# Pressure_Sensor_Breakout.net
KiCad netlist of a schematic drawn in Altium Designer
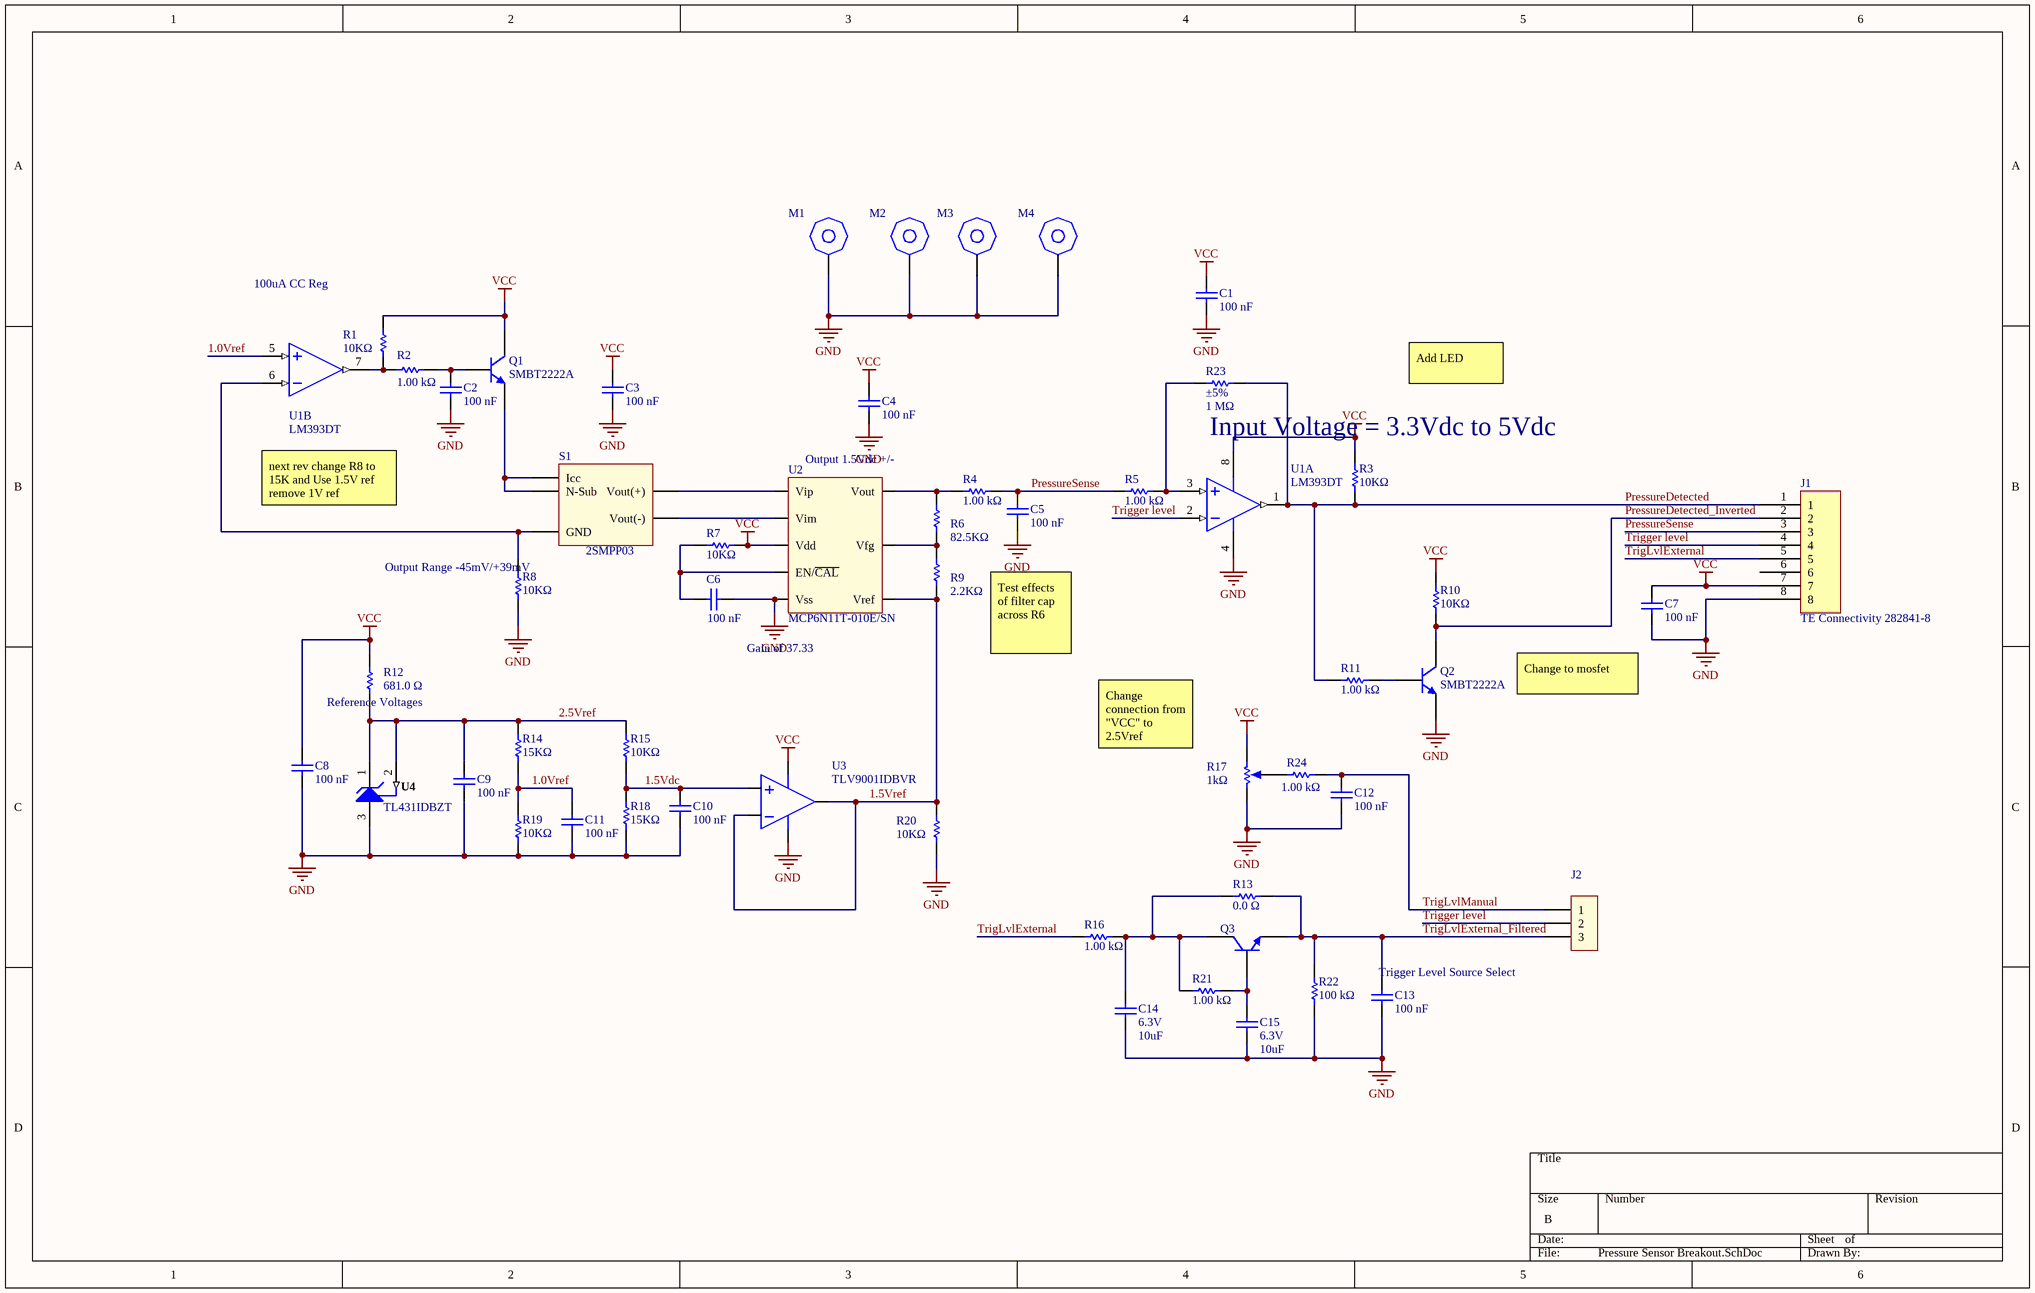
[diagram p0: Pressure Sensor Breakout.SchDoc]

(export (version "E")
  (design (tool "Eeschema 10.0.6"))
  (components
    (comp (ref "C1")
      (value "08055C104JAT2A")
      (footprint "Cap,0805")
      (description "Capacitor; Ceramic; Cap 0.1 uF; Tol 5%; Vol-Rtg 50 VDC; SMT; 0805; X7R; Tape & Reel")
      (fields (field (name "CAPACITANCE") "100 nF"))
      (libsource (lib "Master JULY2019") (part "Cap,0805,100nf,50V,5%,08055C104JAT2A"))
    )
    (comp (ref "C2")
      (value "08055C104JAT2A")
      (footprint "Cap,0805")
      (description "Capacitor; Ceramic; Cap 0.1 uF; Tol 5%; Vol-Rtg 50 VDC; SMT; 0805; X7R; Tape & Reel")
      (fields (field (name "CAPACITANCE") "100 nF"))
      (libsource (lib "Master JULY2019") (part "Cap,0805,100nf,50V,5%,08055C104JAT2A"))
    )
    (comp (ref "C3")
      (value "08055C104JAT2A")
      (footprint "Cap,0805")
      (description "Capacitor; Ceramic; Cap 0.1 uF; Tol 5%; Vol-Rtg 50 VDC; SMT; 0805; X7R; Tape & Reel")
      (fields (field (name "CAPACITANCE") "100 nF"))
      (libsource (lib "Master JULY2019") (part "Cap,0805,100nf,50V,5%,08055C104JAT2A"))
    )
    (comp (ref "C4")
      (value "08055C104JAT2A")
      (footprint "Cap,0805")
      (description "Capacitor; Ceramic; Cap 0.1 uF; Tol 5%; Vol-Rtg 50 VDC; SMT; 0805; X7R; Tape & Reel")
      (fields (field (name "CAPACITANCE") "100 nF"))
      (libsource (lib "Master JULY2019") (part "Cap,0805,100nf,50V,5%,08055C104JAT2A"))
    )
    (comp (ref "C5")
      (value "08055C104JAT2A")
      (footprint "Cap,0805")
      (description "Capacitor; Ceramic; Cap 0.1 uF; Tol 5%; Vol-Rtg 50 VDC; SMT; 0805; X7R; Tape & Reel")
      (fields (field (name "CAPACITANCE") "100 nF"))
      (libsource (lib "Master JULY2019") (part "Cap,0805,100nf,50V,5%,08055C104JAT2A"))
    )
    (comp (ref "C6")
      (value "08055C104JAT2A")
      (footprint "Cap,0805")
      (description "Capacitor; Ceramic; Cap 0.1 uF; Tol 5%; Vol-Rtg 50 VDC; SMT; 0805; X7R; Tape & Reel")
      (fields (field (name "CAPACITANCE") "100 nF"))
      (libsource (lib "Master JULY2019") (part "Cap,0805,100nf,50V,5%,08055C104JAT2A"))
    )
    (comp (ref "C7")
      (value "08055C104JAT2A")
      (footprint "Cap,0805")
      (description "Capacitor; Ceramic; Cap 0.1 uF; Tol 5%; Vol-Rtg 50 VDC; SMT; 0805; X7R; Tape & Reel")
      (fields (field (name "CAPACITANCE") "100 nF"))
      (libsource (lib "Master JULY2019") (part "Cap,0805,100nf,50V,5%,08055C104JAT2A"))
    )
    (comp (ref "C8")
      (value "08055C104JAT2A")
      (footprint "Cap,0805")
      (description "Capacitor; Ceramic; Cap 0.1 uF; Tol 5%; Vol-Rtg 50 VDC; SMT; 0805; X7R; Tape & Reel")
      (fields (field (name "CAPACITANCE") "100 nF"))
      (libsource (lib "Master JULY2019") (part "Cap,0805,100nf,50V,5%,08055C104JAT2A"))
    )
    (comp (ref "C9")
      (value "08055C104JAT2A")
      (footprint "Cap,0805")
      (description "Capacitor; Ceramic; Cap 0.1 uF; Tol 5%; Vol-Rtg 50 VDC; SMT; 0805; X7R; Tape & Reel")
      (fields (field (name "CAPACITANCE") "100 nF"))
      (libsource (lib "Master JULY2019") (part "Cap,0805,100nf,50V,5%,08055C104JAT2A"))
    )
    (comp (ref "C10")
      (value "08055C104JAT2A")
      (footprint "Cap,0805")
      (description "Capacitor; Ceramic; Cap 0.1 uF; Tol 5%; Vol-Rtg 50 VDC; SMT; 0805; X7R; Tape & Reel")
      (fields (field (name "CAPACITANCE") "100 nF"))
      (libsource (lib "Master JULY2019") (part "Cap,0805,100nf,50V,5%,08055C104JAT2A"))
    )
    (comp (ref "C11")
      (value "08055C104JAT2A")
      (footprint "Cap,0805")
      (description "Capacitor; Ceramic; Cap 0.1 uF; Tol 5%; Vol-Rtg 50 VDC; SMT; 0805; X7R; Tape & Reel")
      (fields (field (name "CAPACITANCE") "100 nF"))
      (libsource (lib "Master JULY2019") (part "Cap,0805,100nf,50V,5%,08055C104JAT2A"))
    )
    (comp (ref "C12")
      (value "08055C104JAT2A")
      (footprint "Cap,0805")
      (description "Capacitor; Ceramic; Cap 0.1 uF; Tol 5%; Vol-Rtg 50 VDC; SMT; 0805; X7R; Tape & Reel")
      (fields (field (name "CAPACITANCE") "100 nF"))
      (libsource (lib "Master JULY2019") (part "Cap,0805,100nf,50V,5%,08055C104JAT2A"))
    )
    (comp (ref "C13")
      (value "08055C104JAT2A")
      (footprint "Cap,0805")
      (description "Capacitor; Ceramic; Cap 0.1 uF; Tol 5%; Vol-Rtg 50 VDC; SMT; 0805; X7R; Tape & Reel")
      (fields (field (name "CAPACITANCE") "100 nF"))
      (libsource (lib "Master JULY2019") (part "Cap,0805,100nf,50V,5%,08055C104JAT2A"))
    )
    (comp (ref "C14")
      (value "Cap")
      (footprint "Cap,0805")
      (description "CL21 Series 10 uF 6.3V ±10 % Tolerance X5R SMT Multilayer Ceramic Capacitor")
      (fields
        (field (name "TOLERANCE") "±10%")
        (field (name "VOLTAGE - RATED") "6.3V")
        (field (name "CAPACITANCE") "10uF")
      )
      (libsource (lib "Master JUL_2019-Shawn") (part "Cap,0805,10uf,6.3V,10%,CL21A106KQFNNNG"))
    )
    (comp (ref "C15")
      (value "Cap")
      (footprint "Cap,0805")
      (description "CL21 Series 10 uF 6.3V ±10 % Tolerance X5R SMT Multilayer Ceramic Capacitor")
      (fields
        (field (name "TOLERANCE") "±10%")
        (field (name "VOLTAGE - RATED") "6.3V")
        (field (name "CAPACITANCE") "10uF")
      )
      (libsource (lib "Master JUL_2019-Shawn") (part "Cap,0805,10uf,6.3V,10%,CL21A106KQFNNNG"))
    )
    (comp (ref "J1")
      (value "TE Connectivity 282841-8")
      (footprint "Conn, wire to pcb terminal,282841-8")
      (description "Buchanan; Conn; Term Blk; PCB; 8; 5.08 mm; 30-12 AWG; Green; 17.5 A; 300 V")
      (fields (field (name "MANUFACTURER PART NUMBER") "282841-8"))
      (libsource (lib "Master JULY2019") (part "Connector, Terminal, PCB, 8 Pos,282841-8"))
    )
    (comp (ref "J2")
      (value "Generic Header")
      (footprint "Header,3POS,0.1\",Vert")
      (description "Generic Header 3 pos header 0.1\"")
      (libsource (lib "Master JULY2019") (part "Header 1x3,0.1{dblquote},TH,Generic"))
    )
    (comp (ref "M1")
      (value "M3 hex Standoff")
      (footprint "Standoff,Hex,M3,8mm")
      (description "HEX STANDOFF M3,generic")
      (libsource (lib "Master JULY2019") (part "Mech,Standoff, M3, Hex"))
    )
    (comp (ref "M2")
      (value "M3 hex Standoff")
      (footprint "Standoff,Hex,M3,8mm")
      (description "HEX STANDOFF M3,generic")
      (libsource (lib "Master JULY2019") (part "Mech,Standoff, M3, Hex"))
    )
    (comp (ref "M3")
      (value "M3 hex Standoff")
      (footprint "Standoff,Hex,M3,8mm")
      (description "HEX STANDOFF M3,generic")
      (libsource (lib "Master JULY2019") (part "Mech,Standoff, M3, Hex"))
    )
    (comp (ref "M4")
      (value "M3 hex Standoff")
      (footprint "Standoff,Hex,M3,8mm")
      (description "HEX STANDOFF M3,generic")
      (libsource (lib "Master JULY2019") (part "Mech,Standoff, M3, Hex"))
    )
    (comp (ref "Q1")
      (value "SMBT2222A")
      (footprint "SOT23-3")
      (description "NPN Silicon Switching Transistor, 40 V VCEO, 600 mA IC, SOT23, Reel, Green")
      (fields (field (name "MFG P/N") "SMBT2222A"))
      (libsource (lib "Master JULY2019") (part "Trans,40V,600mA,0.33W, SMBT2222A"))
    )
    (comp (ref "Q2")
      (value "SMBT2222A")
      (footprint "SOT23-3")
      (description "NPN Silicon Switching Transistor, 40 V VCEO, 600 mA IC, SOT23, Reel, Green")
      (fields (field (name "MFG P/N") "SMBT2222A"))
      (libsource (lib "Master JULY2019") (part "Trans,40V,600mA,0.33W, SMBT2222A"))
    )
    (comp (ref "Q3")
      (value "NPN")
      (footprint "SOT23-3")
      (description "NPN Silicon Switching Transistor, 40 V VCEO, 600 mA IC, SOT23, Reel, Green")
      (libsource (lib "Master JUL_2019-Shawn") (part "Trans,40V,600mA,0.33W, SMBT2222A"))
    )
    (comp (ref "R1")
      (value "Vishay / Dale CRCW080510K0FKTA")
      (footprint "res, 0805, HD")
      (description "RES SMD 10K OHM 1% 1/8W 0805")
      (fields (field (name "RESISTANCE") "10KΩ"))
      (libsource (lib "Master JULY2019") (part "Res,0805,10.0kΩ,1%,100 ppm,CRCW080510K0FKTA"))
    )
    (comp (ref "R2")
      (value "Vishay CRCW08051K00JNEA")
      (footprint "res, 0805, HD")
      (description "Res Thick Film 0805 1K Ohm 5% 0.125W(1/8W) ±200ppm/C Molded SMD Automotive Paper T/R")
      (fields
        (field (name "MANUFACTURER PART NUMBER") "CRCW08051K00JNEA")
        (field (name "RESISTANCE") "1.00 kΩ")
      )
      (libsource (lib "Master JULY2019") (part "Res,0805,1.00 kΩ,5%,200ppm,CRCW08051K00JNEA"))
    )
    (comp (ref "R3")
      (value "Vishay / Dale CRCW080510K0FKTA")
      (footprint "res, 0805, HD")
      (description "RES SMD 10K OHM 1% 1/8W 0805")
      (fields (field (name "RESISTANCE") "10KΩ"))
      (libsource (lib "Master JULY2019") (part "Res,0805,10.0kΩ,1%,100 ppm,CRCW080510K0FKTA"))
    )
    (comp (ref "R4")
      (value "Vishay CRCW08051K00JNEA")
      (footprint "res, 0805, HD")
      (description "Res Thick Film 0805 1K Ohm 5% 0.125W(1/8W) ±200ppm/C Molded SMD Automotive Paper T/R")
      (fields
        (field (name "MANUFACTURER PART NUMBER") "CRCW08051K00JNEA")
        (field (name "RESISTANCE") "1.00 kΩ")
      )
      (libsource (lib "Master JULY2019") (part "Res,0805,1.00 kΩ,5%,200ppm,CRCW08051K00JNEA"))
    )
    (comp (ref "R5")
      (value "Vishay CRCW08051K00JNEA")
      (footprint "res, 0805, HD")
      (description "Res Thick Film 0805 1K Ohm 5% 0.125W(1/8W) ±200ppm/C Molded SMD Automotive Paper T/R")
      (fields
        (field (name "MANUFACTURER PART NUMBER") "CRCW08051K00JNEA")
        (field (name "RESISTANCE") "1.00 kΩ")
      )
      (libsource (lib "Master JULY2019") (part "Res,0805,1.00 kΩ,5%,200ppm,CRCW08051K00JNEA"))
    )
    (comp (ref "R6")
      (value "TNPW080582K5BEEA")
      (footprint "res, 0805, HD")
      (fields
        (field (name "MANUFACTURER") "Vishay Dale")
        (field (name "TOLERANCE") "±0.1%")
        (field (name "RESISTANCE") "82.5KΩ")
      )
      (libsource (lib "Master JULY2019") (part "Res,0805,82.5KΩ,0.1%,25ppm, TNPW080582K5BEEA"))
    )
    (comp (ref "R7")
      (value "Vishay / Dale CRCW080510K0FKTA")
      (footprint "res, 0805, HD")
      (description "RES SMD 10K OHM 1% 1/8W 0805")
      (fields (field (name "RESISTANCE") "10KΩ"))
      (libsource (lib "Master JULY2019") (part "Res,0805,10.0kΩ,1%,100 ppm,CRCW080510K0FKTA"))
    )
    (comp (ref "R8")
      (value "Vishay / Dale CRCW080510K0FKTA")
      (footprint "res, 0805, HD")
      (description "RES SMD 10K OHM 1% 1/8W 0805")
      (fields (field (name "RESISTANCE") "10KΩ"))
      (libsource (lib "Master JULY2019") (part "Res,0805,10.0kΩ,1%,100 ppm,CRCW080510K0FKTA"))
    )
    (comp (ref "R9")
      (value "CRCW08052K20FKEA")
      (footprint "res, 0805, HD")
      (description "RES SMD 2.2K OHM 1% 1/8W 0805")
      (fields (field (name "RESISTANCE") "2.2KΩ"))
      (libsource (lib "Master JULY2019") (part "Res,0805,2.2KΩ,±1%,100.0 ppm/°C,150.0 V,CRCW08052K20FKEA"))
    )
    (comp (ref "R10")
      (value "Vishay / Dale CRCW080510K0FKTA")
      (footprint "res, 0805, HD")
      (description "RES SMD 10K OHM 1% 1/8W 0805")
      (fields (field (name "RESISTANCE") "10KΩ"))
      (libsource (lib "Master JULY2019") (part "Res,0805,10.0kΩ,1%,100 ppm,CRCW080510K0FKTA"))
    )
    (comp (ref "R11")
      (value "Vishay CRCW08051K00JNEA")
      (footprint "res, 0805, HD")
      (description "Res Thick Film 0805 1K Ohm 5% 0.125W(1/8W) ±200ppm/C Molded SMD Automotive Paper T/R")
      (fields
        (field (name "MANUFACTURER PART NUMBER") "CRCW08051K00JNEA")
        (field (name "RESISTANCE") "1.00 kΩ")
      )
      (libsource (lib "Master JULY2019") (part "Res,0805,1.00 kΩ,5%,200ppm,CRCW08051K00JNEA"))
    )
    (comp (ref "R12")
      (value "CRCW0805681RFKEA")
      (footprint "res, 0805, HD")
      (description "RES SMD 681 OHM 1% 1/8W 0805")
      (fields (field (name "RESISTANCE") "681.0 Ω"))
      (libsource (lib "Master JULY2019") (part "Res,0805,681.0 Ω,±1%,100.0 ppm/°C,150.0 V,CRCW0805681RFKEA"))
    )
    (comp (ref "R13")
      (value "Res1")
      (footprint "res, 0805, HD")
      (description "RES SMD 0.0 OHM JUMPER 1/3W 0805")
      (fields (field (name "RESISTANCE") "0.0 Ω"))
      (libsource (lib "Master JULY2019") (part "Res,0805,0.0Ω,150V"))
    )
    (comp (ref "R14")
      (value "CRGCQ0805F15K")
      (footprint "res, 0805, HD")
      (fields (field (name "TOLERANCE") "±1%") (field (name "RESISTANCE") "15KΩ"))
      (libsource (lib "Master JULY2019") (part "Res,0805,15KΩ,1%,±100ppm/°C,CRGCQ0805F15K"))
    )
    (comp (ref "R15")
      (value "Vishay / Dale CRCW080510K0FKTA")
      (footprint "res, 0805, HD")
      (description "RES SMD 10K OHM 1% 1/8W 0805")
      (fields (field (name "RESISTANCE") "10KΩ"))
      (libsource (lib "Master JULY2019") (part "Res,0805,10.0kΩ,1%,100 ppm,CRCW080510K0FKTA"))
    )
    (comp (ref "R16")
      (value "Vishay CRCW08051K00JNEA")
      (footprint "res, 0805, HD")
      (description "Res Thick Film 0805 1K Ohm 5% 0.125W(1/8W) ±200ppm/C Molded SMD Automotive Paper T/R")
      (fields
        (field (name "MANUFACTURER PART NUMBER") "CRCW08051K00JNEA")
        (field (name "RESISTANCE") "1.00 kΩ")
      )
      (libsource (lib "Master JULY2019") (part "Res,0805,1.00 kΩ,5%,200ppm,CRCW08051K00JNEA"))
    )
    (comp (ref "R17")
      (value "TC33X-2-102E")
      (footprint "Res,SMD,POT,TC33 Series")
      (description "TRIMMER 1k OHM 0.1W J LEAD TOP")
      (fields
        (field (name "MANUFACTURER") "Bourns Inc.")
        (field (name "TOLERANCE") "±25%")
        (field (name "RESISTANCE") "1kΩ")
      )
      (libsource (lib "Master JULY2019") (part "Res,POT,SMD,1kΩ,0.1W, TC33X-2-102E"))
    )
    (comp (ref "R18")
      (value "CRGCQ0805F15K")
      (footprint "res, 0805, HD")
      (fields (field (name "TOLERANCE") "±1%") (field (name "RESISTANCE") "15KΩ"))
      (libsource (lib "Master JULY2019") (part "Res,0805,15KΩ,1%,±100ppm/°C,CRGCQ0805F15K"))
    )
    (comp (ref "R19")
      (value "Vishay / Dale CRCW080510K0FKTA")
      (footprint "res, 0805, HD")
      (description "RES SMD 10K OHM 1% 1/8W 0805")
      (fields (field (name "RESISTANCE") "10KΩ"))
      (libsource (lib "Master JULY2019") (part "Res,0805,10.0kΩ,1%,100 ppm,CRCW080510K0FKTA"))
    )
    (comp (ref "R20")
      (value "Vishay / Dale CRCW080510K0FKTA")
      (footprint "res, 0805, HD")
      (description "RES SMD 10K OHM 1% 1/8W 0805")
      (fields (field (name "RESISTANCE") "10KΩ"))
      (libsource (lib "Master JULY2019") (part "Res,0805,10.0kΩ,1%,100 ppm,CRCW080510K0FKTA"))
    )
    (comp (ref "R21")
      (value "Vishay CRCW08051K00JNEA")
      (footprint "res, 0805, HD")
      (description "Res Thick Film 0805 1K Ohm 5% 0.125W(1/8W) ±200ppm/C Molded SMD Automotive Paper T/R")
      (fields
        (field (name "MANUFACTURER PART NUMBER") "CRCW08051K00JNEA")
        (field (name "RESISTANCE") "1.00 kΩ")
      )
      (libsource (lib "Master JULY2019") (part "Res,0805,1.00 kΩ,5%,200ppm,CRCW08051K00JNEA"))
    )
    (comp (ref "R22")
      (value "Res,0805,100kΩ,1%,100ppm,CRCW0805100KFKEA")
      (footprint "res, 0805, HD")
      (description "100 kOhms ±1% 0.125W, 1/8W Chip Resistor 0805 (2012 Metric) Thick Film")
      (fields
        (field (name "MANUFACTURER PART NUMBER") "CRCW0805100KFKEA")
        (field (name "MANUFACTURER") "Vishay")
        (field (name "RESISTANCE") "100 kΩ")
      )
      (libsource (lib "Master JULY2019") (part "Res,0805,100kΩ,1%,100ppm,CRCW0805100KFKEA"))
    )
    (comp (ref "R23")
      (value "CR0805-JW-105ELF")
      (footprint "res, 0805, HD")
      (description "RES SMD 1M OHM 5% 1/8W 0805")
      (fields
        (field (name "MANUFACTURER") "Bourns Inc.")
        (field (name "JLC ALT LCSC PART #") "C26108")
        (field (name "TOLERANCE") "±5%")
        (field (name "RESISTANCE") "1 MΩ")
      )
      (libsource (lib "Master JULY2019") (part "Res,0805,1MegΩ,5%,200ppm,0805W8F1005T5E"))
    )
    (comp (ref "R24")
      (value "Vishay CRCW08051K00JNEA")
      (footprint "res, 0805, HD")
      (description "Res Thick Film 0805 1K Ohm 5% 0.125W(1/8W) ±200ppm/C Molded SMD Automotive Paper T/R")
      (fields
        (field (name "MANUFACTURER PART NUMBER") "CRCW08051K00JNEA")
        (field (name "RESISTANCE") "1.00 kΩ")
      )
      (libsource (lib "Master JULY2019") (part "Res,0805,1.00 kΩ,5%,200ppm,CRCW08051K00JNEA"))
    )
    (comp (ref "S1")
      (value "2SMPP03")
      (footprint "2SMPP03,6-SMD Module")
      (description "SENSOR PRESSURE -50-50 KPA PCB")
      (fields
        (field (name "MANUFACTURER") "Omron Electronics Inc-EMC Div")
        (field (name "MFG P/N") "2SMPP03")
      )
      (libsource (lib "Master JULY2019") (part "Sensor,PRESSURE,Air, ±7.25PSI, 2SMPP03"))
    )
    (comp (ref "U1")
      (value "LM393DT")
      (footprint "SOIC-8")
      (description "IC COMPARATOR LP DUAL 8-SOIC")
      (fields (field (name "MANUFACTURER") "STMicroelectronics") (field (name "BASE PART NUMBER") "LM393"))
      (libsource (lib "Master JULY2019") (part "OPAMP,DUAL,COMAPRATOR,SOIC8,OPEN-COLLECTOR,LM393DT"))
    )
    (comp (ref "U2")
      (value "MCP6N11T-010E/SN")
      (footprint "SOIC-8")
      (description "IC INST AMP 1 CIRCUIT 8SOIC")
      (fields
        (field (name "MFG P/N") "MCP6N11T-010E/SN")
        (field (name "MANUFACTURER") "Microchip Technology")
      )
      (libsource (lib "Master JULY2019") (part "Opamp,Instrumentation,SOIC,5Mhz,RailToRail, MCP6N11T-010E/SN"))
    )
    (comp (ref "U3")
      (value "TLV9001IDBVR")
      (footprint "SOT23-5")
      (description "IC CMOS 1 CIRCUIT SOT23-5")
      (fields (field (name "MFG P/N") "TLV9001IDBVR") (field (name "MANUFACTURER") "Texas Instruments"))
      (libsource (lib "Master JULY2019") (part "OPAMP,Single,1Mhz,RailToRail,SOT-5, TLV9001IDBVR"))
    )
    (comp (ref "U4")
      (value "Shunt Regulator,2.5Vdc TL431IDBZT")
      (footprint "SOT23-3")
      (fields (field (name "MANUFACTURER PART NUMBER") "TL431IDBZT"))
      (libsource (lib "Master JULY2019") (part "Shunt Regulator,2.5Vdc TL431IDBZT"))
    )
  )
  (nets
    (net (code "1") (name "/1.0Vref") (class "Default")
      (node (ref "C11") (pin "1") (pinfunction "1_1") (pintype "passive"))
      (node (ref "R14") (pin "1") (pinfunction "1_1") (pintype "passive"))
      (node (ref "R19") (pin "2") (pinfunction "2_2") (pintype "passive"))
      (node (ref "U1") (pin "5") (pinfunction "IN2+_5") (pintype "input"))
    )
    (net (code "2") (name "/1.5Vdc") (class "Default")
      (node (ref "C10") (pin "1") (pinfunction "1_1") (pintype "passive"))
      (node (ref "R15") (pin "1") (pinfunction "1_1") (pintype "passive"))
      (node (ref "R18") (pin "2") (pinfunction "2_2") (pintype "passive"))
      (node (ref "U3") (pin "3") (pinfunction "IN+_3") (pintype "passive"))
    )
    (net (code "3") (name "/1.5Vref") (class "Default")
      (node (ref "R20") (pin "2") (pinfunction "2_2") (pintype "passive"))
      (node (ref "R9") (pin "1") (pinfunction "1_1") (pintype "passive"))
      (node (ref "U2") (pin "5") (pinfunction "Vref_5") (pintype "passive"))
      (node (ref "U3") (pin "1") (pinfunction "Out_1") (pintype "passive"))
      (node (ref "U3") (pin "4") (pinfunction "IN-_4") (pintype "passive"))
    )
    (net (code "4") (name "/2.5Vref") (class "Default")
      (node (ref "C9") (pin "1") (pinfunction "1_1") (pintype "passive"))
      (node (ref "R12") (pin "1") (pinfunction "1_1") (pintype "passive"))
      (node (ref "R14") (pin "2") (pinfunction "2_2") (pintype "passive"))
      (node (ref "R15") (pin "2") (pinfunction "2_2") (pintype "passive"))
      (node (ref "U4") (pin "1") (pinfunction "CATHODE_1") (pintype "passive"))
      (node (ref "U4") (pin "2") (pinfunction "REF_2") (pintype "input"))
    )
    (net (code "5") (name "/PressureDetected") (class "Default")
      (node (ref "J1") (pin "1") (pinfunction "1_1") (pintype "passive"))
      (node (ref "R11") (pin "2") (pinfunction "2_2") (pintype "passive"))
      (node (ref "R23") (pin "1") (pinfunction "1_1") (pintype "passive"))
      (node (ref "R3") (pin "1") (pinfunction "1_1") (pintype "passive"))
      (node (ref "U1") (pin "1") (pinfunction "OUT1_1") (pintype "output"))
    )
    (net (code "6") (name "/PressureDetected_Inverted") (class "Default")
      (node (ref "J1") (pin "2") (pinfunction "2_2") (pintype "passive"))
      (node (ref "Q2") (pin "3") (pinfunction "C_3") (pintype "passive"))
      (node (ref "R10") (pin "1") (pinfunction "1_1") (pintype "passive"))
    )
    (net (code "7") (name "/PressureSense") (class "Default")
      (node (ref "C5") (pin "1") (pinfunction "1_1") (pintype "passive"))
      (node (ref "J1") (pin "3") (pinfunction "3_3") (pintype "passive"))
      (node (ref "R4") (pin "1") (pinfunction "1_1") (pintype "passive"))
      (node (ref "R5") (pin "1") (pinfunction "1_1") (pintype "passive"))
    )
    (net (code "8") (name "/TrigLvlExternal") (class "Default")
      (node (ref "J1") (pin "5") (pinfunction "5_5") (pintype "passive"))
      (node (ref "R16") (pin "1") (pinfunction "1_1") (pintype "passive"))
    )
    (net (code "9") (name "/TrigLvlExternal_Filtered") (class "Default")
      (node (ref "C13") (pin "1") (pinfunction "1_1") (pintype "passive"))
      (node (ref "J2") (pin "3") (pinfunction "3_3") (pintype "passive"))
      (node (ref "Q3") (pin "3") (pinfunction "E_3") (pintype "passive"))
      (node (ref "R13") (pin "1") (pinfunction "1_1") (pintype "passive"))
      (node (ref "R22") (pin "2") (pinfunction "2_2") (pintype "passive"))
    )
    (net (code "10") (name "/TrigLvlManual") (class "Default")
      (node (ref "C12") (pin "1") (pinfunction "1_1") (pintype "passive"))
      (node (ref "J2") (pin "1") (pinfunction "1_1") (pintype "passive"))
      (node (ref "R24") (pin "1") (pinfunction "1_1") (pintype "passive"))
    )
    (net (code "11") (name "/Trigger level") (class "Default")
      (node (ref "J1") (pin "4") (pinfunction "4_4") (pintype "passive"))
      (node (ref "J2") (pin "2") (pinfunction "2_2") (pintype "passive"))
      (node (ref "U1") (pin "2") (pinfunction "IN1-_2") (pintype "input"))
    )
    (net (code "12") (name "GND") (class "Default")
      (node (ref "C1") (pin "2") (pinfunction "2_2") (pintype "passive"))
      (node (ref "C10") (pin "2") (pinfunction "2_2") (pintype "passive"))
      (node (ref "C11") (pin "2") (pinfunction "2_2") (pintype "passive"))
      (node (ref "C12") (pin "2") (pinfunction "2_2") (pintype "passive"))
      (node (ref "C13") (pin "2") (pinfunction "2_2") (pintype "passive"))
      (node (ref "C14") (pin "1") (pinfunction "1_1") (pintype "passive"))
      (node (ref "C15") (pin "1") (pinfunction "1_1") (pintype "passive"))
      (node (ref "C2") (pin "2") (pinfunction "2_2") (pintype "passive"))
      (node (ref "C3") (pin "2") (pinfunction "2_2") (pintype "passive"))
      (node (ref "C4") (pin "2") (pinfunction "2_2") (pintype "passive"))
      (node (ref "C5") (pin "2") (pinfunction "2_2") (pintype "passive"))
      (node (ref "C6") (pin "1") (pinfunction "1_1") (pintype "passive"))
      (node (ref "C7") (pin "2") (pinfunction "2_2") (pintype "passive"))
      (node (ref "C8") (pin "2") (pinfunction "2_2") (pintype "passive"))
      (node (ref "C9") (pin "2") (pinfunction "2_2") (pintype "passive"))
      (node (ref "J1") (pin "8") (pinfunction "8_8") (pintype "passive"))
      (node (ref "M1") (pin "0") (pinfunction "0_0") (pintype "passive"))
      (node (ref "M2") (pin "0") (pinfunction "0_0") (pintype "passive"))
      (node (ref "M3") (pin "0") (pinfunction "0_0") (pintype "passive"))
      (node (ref "M4") (pin "0") (pinfunction "0_0") (pintype "passive"))
      (node (ref "Q2") (pin "2") (pinfunction "E_2") (pintype "passive"))
      (node (ref "R17") (pin "1") (pinfunction "1_1") (pintype "passive"))
      (node (ref "R18") (pin "1") (pinfunction "1_1") (pintype "passive"))
      (node (ref "R19") (pin "1") (pinfunction "1_1") (pintype "passive"))
      (node (ref "R20") (pin "1") (pinfunction "1_1") (pintype "passive"))
      (node (ref "R22") (pin "1") (pinfunction "1_1") (pintype "passive"))
      (node (ref "R8") (pin "1") (pinfunction "1_1") (pintype "passive"))
      (node (ref "U1") (pin "4") (pinfunction "Gnd_4") (pintype "power_in"))
      (node (ref "U2") (pin "4") (pinfunction "Vss_4") (pintype "passive"))
      (node (ref "U3") (pin "2") (pinfunction "V-_2") (pintype "passive"))
      (node (ref "U4") (pin "3") (pinfunction "ANODE_3") (pintype "passive"))
    )
    (net (code "13") (name "Net-(Q1-B)") (class "Default")
      (node (ref "C2") (pin "1") (pinfunction "1_1") (pintype "passive"))
      (node (ref "Q1") (pin "1") (pinfunction "B_1") (pintype "passive"))
      (node (ref "R2") (pin "1") (pinfunction "1_1") (pintype "passive"))
    )
    (net (code "14") (name "Net-(Q1-E)") (class "Default")
      (node (ref "Q1") (pin "2") (pinfunction "E_2") (pintype "passive"))
      (node (ref "S1") (pin "5") (pinfunction "N-Sub_5") (pintype "passive"))
      (node (ref "S1") (pin "6") (pinfunction "Icc_6") (pintype "passive"))
    )
    (net (code "15") (name "Net-(Q2-B)") (class "Default")
      (node (ref "Q2") (pin "1") (pinfunction "B_1") (pintype "passive"))
      (node (ref "R11") (pin "1") (pinfunction "1_1") (pintype "passive"))
    )
    (net (code "16") (name "Net-(Q3-B)") (class "Default")
      (node (ref "C15") (pin "2") (pinfunction "2_2") (pintype "passive"))
      (node (ref "Q3") (pin "2") (pinfunction "B_2") (pintype "passive"))
      (node (ref "R21") (pin "1") (pinfunction "1_1") (pintype "passive"))
    )
    (net (code "17") (name "Net-(Q3-C)") (class "Default")
      (node (ref "C14") (pin "2") (pinfunction "2_2") (pintype "passive"))
      (node (ref "Q3") (pin "1") (pinfunction "C_1") (pintype "passive"))
      (node (ref "R13") (pin "2") (pinfunction "2_2") (pintype "passive"))
      (node (ref "R16") (pin "2") (pinfunction "2_2") (pintype "passive"))
      (node (ref "R21") (pin "2") (pinfunction "2_2") (pintype "passive"))
    )
    (net (code "18") (name "Net-(R17-Pad2)") (class "Default")
      (node (ref "R17") (pin "2") (pinfunction "2_2") (pintype "passive"))
      (node (ref "R24") (pin "2") (pinfunction "2_2") (pintype "passive"))
    )
    (net (code "19") (name "Net-(S1-GND)") (class "Default")
      (node (ref "R8") (pin "2") (pinfunction "2_2") (pintype "passive"))
      (node (ref "S1") (pin "3") (pinfunction "GND_3") (pintype "passive"))
      (node (ref "U1") (pin "6") (pinfunction "IN2-_6") (pintype "input"))
    )
    (net (code "20") (name "Net-(S1-Vout(+))") (class "Default")
      (node (ref "S1") (pin "1") (pinfunction "Vout(+)_1") (pintype "passive"))
      (node (ref "U2") (pin "3") (pinfunction "Vip_3") (pintype "passive"))
    )
    (net (code "21") (name "Net-(S1-Vout(-))") (class "Default")
      (node (ref "S1") (pin "4") (pinfunction "Vout(-)_4") (pintype "passive"))
      (node (ref "U2") (pin "2") (pinfunction "Vim_2") (pintype "passive"))
    )
    (net (code "22") (name "Net-(U1A-IN1+)") (class "Default")
      (node (ref "R23") (pin "2") (pinfunction "2_2") (pintype "passive"))
      (node (ref "R5") (pin "2") (pinfunction "2_2") (pintype "passive"))
      (node (ref "U1") (pin "3") (pinfunction "IN1+_3") (pintype "input"))
    )
    (net (code "23") (name "Net-(U1B-OUT2)") (class "Default")
      (node (ref "R1") (pin "1") (pinfunction "1_1") (pintype "passive"))
      (node (ref "R2") (pin "2") (pinfunction "2_2") (pintype "passive"))
      (node (ref "U1") (pin "7") (pinfunction "OUT2_7") (pintype "output"))
    )
    (net (code "24") (name "Net-(U2-EN{slash}~{CAL})") (class "Default")
      (node (ref "C6") (pin "2") (pinfunction "2_2") (pintype "passive"))
      (node (ref "R7") (pin "1") (pinfunction "1_1") (pintype "passive"))
      (node (ref "U2") (pin "8") (pinfunction "EN/~{CAL}_8") (pintype "passive"))
    )
    (net (code "25") (name "Net-(U2-Vfg)") (class "Default")
      (node (ref "R6") (pin "1") (pinfunction "1_1") (pintype "passive"))
      (node (ref "R9") (pin "2") (pinfunction "2_2") (pintype "passive"))
      (node (ref "U2") (pin "1") (pinfunction "Vfg_1") (pintype "passive"))
    )
    (net (code "26") (name "Net-(U2-Vout)") (class "Default")
      (node (ref "R4") (pin "2") (pinfunction "2_2") (pintype "passive"))
      (node (ref "R6") (pin "2") (pinfunction "2_2") (pintype "passive"))
      (node (ref "U2") (pin "6") (pinfunction "Vout_6") (pintype "passive"))
    )
    (net (code "27") (name "VCC") (class "Default")
      (node (ref "C1") (pin "1") (pinfunction "1_1") (pintype "passive"))
      (node (ref "C3") (pin "1") (pinfunction "1_1") (pintype "passive"))
      (node (ref "C4") (pin "1") (pinfunction "1_1") (pintype "passive"))
      (node (ref "C7") (pin "1") (pinfunction "1_1") (pintype "passive"))
      (node (ref "C8") (pin "1") (pinfunction "1_1") (pintype "passive"))
      (node (ref "J1") (pin "7") (pinfunction "7_7") (pintype "passive"))
      (node (ref "Q1") (pin "3") (pinfunction "C_3") (pintype "passive"))
      (node (ref "R1") (pin "2") (pinfunction "2_2") (pintype "passive"))
      (node (ref "R10") (pin "2") (pinfunction "2_2") (pintype "passive"))
      (node (ref "R12") (pin "2") (pinfunction "2_2") (pintype "passive"))
      (node (ref "R17") (pin "3") (pinfunction "3_3") (pintype "passive"))
      (node (ref "R3") (pin "2") (pinfunction "2_2") (pintype "passive"))
      (node (ref "R7") (pin "2") (pinfunction "2_2") (pintype "passive"))
      (node (ref "U1") (pin "8") (pinfunction "Vcc_8") (pintype "power_in"))
      (node (ref "U2") (pin "7") (pinfunction "Vdd_7") (pintype "passive"))
      (node (ref "U3") (pin "5") (pinfunction "V+_5") (pintype "passive"))
    )
    (net (code "28") (name "unconnected-(J1-Pad6)") (class "Default")
      (node (ref "J1") (pin "6") (pinfunction "6_6") (pintype "passive"))
    )
    (net (code "29") (name "unconnected-(S1-NC-Pad2)") (class "Default")
      (node (ref "S1") (pin "2") (pinfunction "NC_2") (pintype "passive"))
    )
  )
)
